# Tiny_UniProg_-_Arduino_Uno.net
KiCad netlist of a schematic drawn in EAGLE
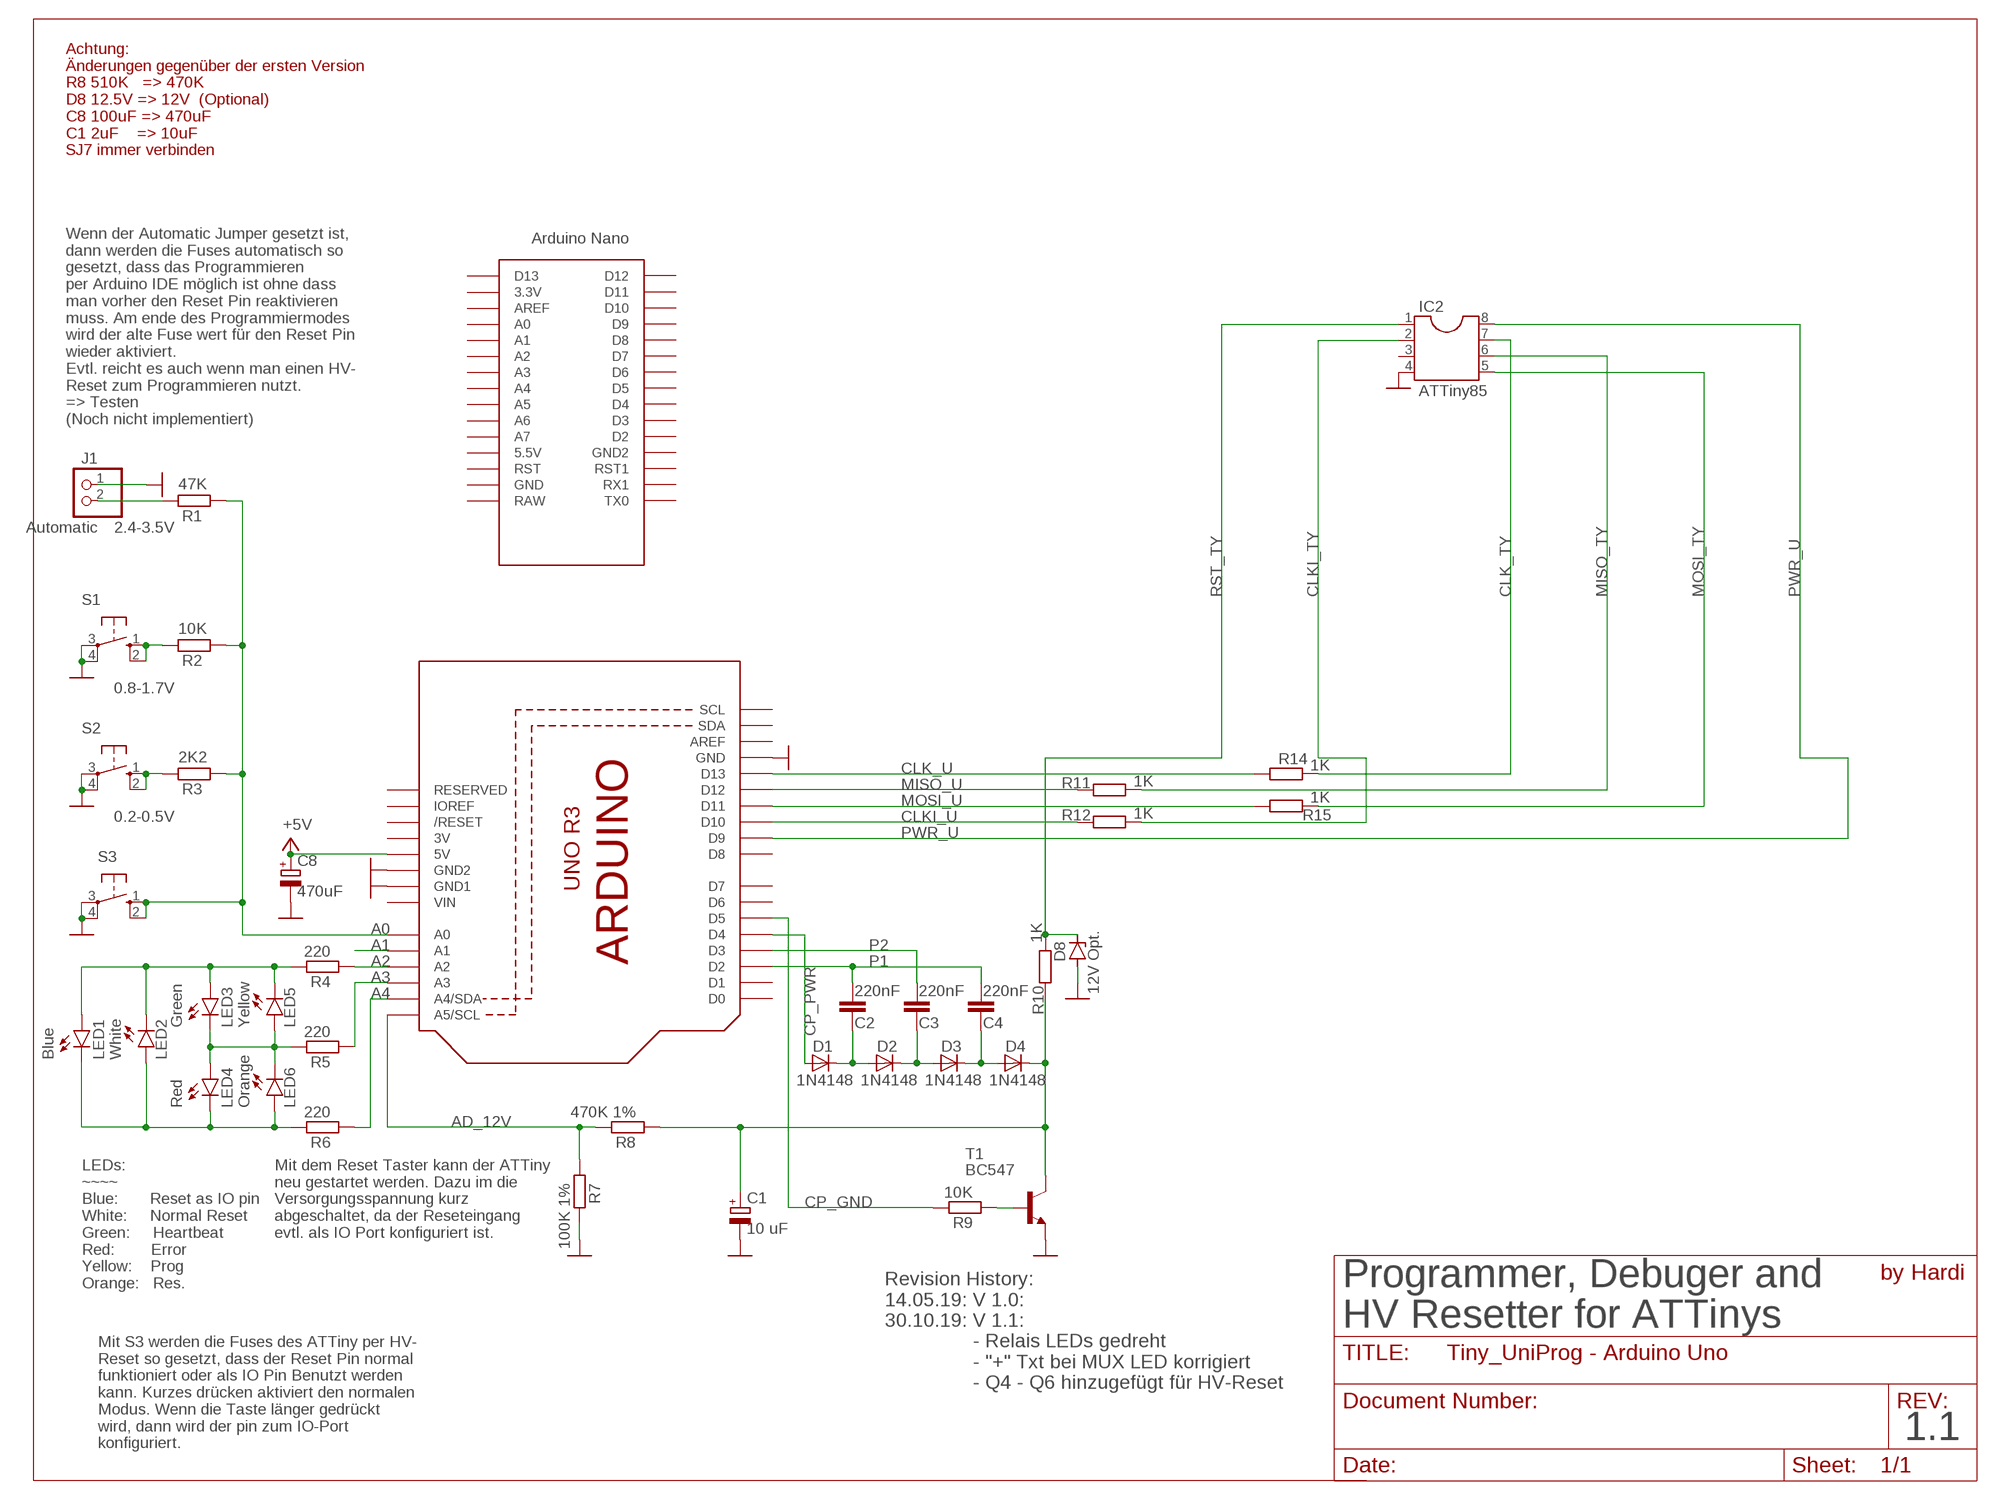
[diagram p0: schematic, sheet 1]

(export (version "E")
  (design (tool "Eeschema 10.0.6"))
  (components
    (comp (ref "C1")
      (value "10 uF")
      (footprint "eagle-import:E5-5")
      (libsource (lib "eagle-import") (part "CPOL-EUE5-5"))
    )
    (comp (ref "C2")
      (value "220nF")
      (footprint "eagle-import:C050-024X044")
      (libsource (lib "eagle-import") (part "C-EU050-024X044"))
    )
    (comp (ref "C3")
      (value "220nF")
      (footprint "eagle-import:C050-024X044")
      (libsource (lib "eagle-import") (part "C-EU050-024X044"))
    )
    (comp (ref "C4")
      (value "220nF")
      (footprint "eagle-import:C050-024X044")
      (libsource (lib "eagle-import") (part "C-EU050-024X044"))
    )
    (comp (ref "C8")
      (value "470uF")
      (footprint "eagle-import:E5-10,5")
      (libsource (lib "eagle-import") (part "CPOL-EUE5-10.5"))
    )
    (comp (ref "D1")
      (value "1N4148")
      (footprint "eagle-import:DO35-2")
      (libsource (lib "eagle-import") (part "1N4148DO35-2"))
    )
    (comp (ref "D2")
      (value "1N4148")
      (footprint "eagle-import:DO35-2")
      (libsource (lib "eagle-import") (part "1N4148DO35-2"))
    )
    (comp (ref "D3")
      (value "1N4148")
      (footprint "eagle-import:DO35-2")
      (libsource (lib "eagle-import") (part "1N4148DO35-2"))
    )
    (comp (ref "D4")
      (value "1N4148")
      (footprint "eagle-import:DO35-2")
      (libsource (lib "eagle-import") (part "1N4148DO35-2"))
    )
    (comp (ref "D8")
      (value "12V Opt.")
      (footprint "eagle-import:ZDIO-2.5")
      (libsource (lib "eagle-import") (part "ZENER-DIODEZD-2.5"))
    )
    (comp (ref "IC2")
      (value "ATTiny85")
      (footprint "eagle-import:DIL08")
      (libsource (lib "eagle-import") (part "DIL8"))
    )
    (comp (ref "J1")
      (value "Automatic")
      (footprint "eagle-import:1X02")
      (libsource (lib "eagle-import") (part "PINHD-1X2"))
    )
    (comp (ref "LED1")
      (value "Blue")
      (footprint "eagle-import:LED3MM")
      (libsource (lib "eagle-import") (part "LED3MM"))
    )
    (comp (ref "LED2")
      (value "White")
      (footprint "eagle-import:LED3MM")
      (libsource (lib "eagle-import") (part "LED3MM"))
    )
    (comp (ref "LED3")
      (value "Green")
      (footprint "eagle-import:LED3MM")
      (libsource (lib "eagle-import") (part "LED3MM"))
    )
    (comp (ref "LED4")
      (value "Red")
      (footprint "eagle-import:LED3MM")
      (libsource (lib "eagle-import") (part "LED3MM"))
    )
    (comp (ref "LED5")
      (value "Yellow")
      (footprint "eagle-import:LED3MM")
      (libsource (lib "eagle-import") (part "LED3MM"))
    )
    (comp (ref "LED6")
      (value "Orange")
      (footprint "eagle-import:LED3MM")
      (libsource (lib "eagle-import") (part "LED3MM"))
    )
    (comp (ref "R1")
      (value "47K")
      (footprint "eagle-import:0204_5")
      (libsource (lib "eagle-import") (part "R-EU_0204/5"))
    )
    (comp (ref "R2")
      (value "10K")
      (footprint "eagle-import:0204V")
      (libsource (lib "eagle-import") (part "R-EU_0204/2V"))
    )
    (comp (ref "R3")
      (value "2K2")
      (footprint "eagle-import:0204V")
      (libsource (lib "eagle-import") (part "R-EU_0204/2V"))
    )
    (comp (ref "R4")
      (value "220")
      (footprint "eagle-import:0204_5")
      (libsource (lib "eagle-import") (part "R-EU_0204/5"))
    )
    (comp (ref "R5")
      (value "220")
      (footprint "eagle-import:0204V")
      (libsource (lib "eagle-import") (part "R-EU_0204/2V"))
    )
    (comp (ref "R6")
      (value "220")
      (footprint "eagle-import:0204_5")
      (libsource (lib "eagle-import") (part "R-EU_0204/5"))
    )
    (comp (ref "R7")
      (value "100K 1%")
      (footprint "eagle-import:0204_7")
      (libsource (lib "eagle-import") (part "R-EU_0204/7"))
    )
    (comp (ref "R8")
      (value "470K 1%")
      (footprint "eagle-import:0204V")
      (libsource (lib "eagle-import") (part "R-EU_0204/2V"))
    )
    (comp (ref "R9")
      (value "10K")
      (footprint "eagle-import:0204_7")
      (libsource (lib "eagle-import") (part "R-EU_0204/7"))
    )
    (comp (ref "R10")
      (value "1K")
      (footprint "eagle-import:0207_15")
      (libsource (lib "eagle-import") (part "R-EU_0207/15"))
    )
    (comp (ref "R11")
      (value "1K")
      (footprint "eagle-import:0204V")
      (libsource (lib "eagle-import") (part "R-EU_0204/2V"))
    )
    (comp (ref "R12")
      (value "1K")
      (footprint "eagle-import:0207_7")
      (libsource (lib "eagle-import") (part "R-EU_0207/7"))
    )
    (comp (ref "R14")
      (value "1K")
      (footprint "eagle-import:0204V")
      (libsource (lib "eagle-import") (part "R-EU_0204/2V"))
    )
    (comp (ref "R15")
      (value "1K")
      (footprint "eagle-import:0204V")
      (libsource (lib "eagle-import") (part "R-EU_0204/2V"))
    )
    (comp (ref "S1")
      (value "10-XX")
      (footprint "eagle-import:B3F-10XX")
      (fields (field (name "MPN") "B3F-1000"))
      (libsource (lib "eagle-import") (part "10-XX"))
    )
    (comp (ref "S2")
      (value "10-XX")
      (footprint "eagle-import:B3F-10XX")
      (fields (field (name "MPN") "B3F-1000"))
      (libsource (lib "eagle-import") (part "10-XX"))
    )
    (comp (ref "S3")
      (value "10-XX")
      (footprint "eagle-import:B3F-10XX")
      (fields (field (name "MPN") "B3F-1000"))
      (libsource (lib "eagle-import") (part "10-XX"))
    )
    (comp (ref "T1")
      (value "BC547")
      (footprint "eagle-import:TO92")
      (libsource (lib "eagle-import") (part "BC547"))
    )
    (comp (ref "U$1")
      (value "NANO")
      (footprint "eagle-import:NANO")
      (libsource (lib "eagle-import") (part "NANO"))
    )
    (comp (ref "U1")
      (value "ARDUINOR3-DIMENSION")
      (footprint "eagle-import:ARDUINOR3")
      (libsource (lib "eagle-import") (part "ARDUINOR3-DIMENSION"))
    )
  )
  (nets
    (net (code "1") (name "+5V") (class "Default")
      (node (ref "C8") (pin "+") (pinfunction "+_+") (pintype "passive"))
      (node (ref "U1") (pin "5V") (pinfunction "5V_5V") (pintype "power_in"))
    )
    (net (code "2") (name "/3V") (class "Default")
      (node (ref "U1") (pin "3V") (pinfunction "3V_3V") (pintype "power_in"))
    )
    (net (code "3") (name "/A0") (class "Default")
      (node (ref "R1") (pin "1") (pinfunction "1_1") (pintype "passive"))
      (node (ref "R2") (pin "1") (pinfunction "1_1") (pintype "passive"))
      (node (ref "R3") (pin "1") (pinfunction "1_1") (pintype "passive"))
      (node (ref "S3") (pin "1") (pinfunction "S_1") (pintype "passive"))
      (node (ref "S3") (pin "2") (pinfunction "S1_2") (pintype "passive"))
      (node (ref "U1") (pin "A0") (pinfunction "A0_A0") (pintype "bidirectional"))
    )
    (net (code "4") (name "/A1") (class "Default")
      (node (ref "U1") (pin "A1") (pinfunction "A1_A1") (pintype "bidirectional"))
    )
    (net (code "5") (name "/A2") (class "Default")
      (node (ref "R4") (pin "1") (pinfunction "1_1") (pintype "passive"))
      (node (ref "U1") (pin "A2") (pinfunction "A2_A2") (pintype "bidirectional"))
    )
    (net (code "6") (name "/A3") (class "Default")
      (node (ref "R5") (pin "1") (pinfunction "1_1") (pintype "passive"))
      (node (ref "U1") (pin "A3") (pinfunction "A3_A3") (pintype "bidirectional"))
    )
    (net (code "7") (name "/A4") (class "Default")
      (node (ref "R6") (pin "1") (pinfunction "1_1") (pintype "passive"))
      (node (ref "U1") (pin "A4") (pinfunction "A4/SDA_A4") (pintype "bidirectional"))
    )
    (net (code "8") (name "/AD_12V") (class "Default")
      (node (ref "R7") (pin "1") (pinfunction "1_1") (pintype "passive"))
      (node (ref "R8") (pin "2") (pinfunction "2_2") (pintype "passive"))
      (node (ref "U1") (pin "A5") (pinfunction "A5/SCL_A5") (pintype "bidirectional"))
    )
    (net (code "9") (name "/CLKI_TY") (class "Default")
      (node (ref "IC2") (pin "2") (pinfunction "2_2") (pintype "passive"))
      (node (ref "R12") (pin "2") (pinfunction "2_2") (pintype "passive"))
    )
    (net (code "10") (name "/CLKI_U") (class "Default")
      (node (ref "R12") (pin "1") (pinfunction "1_1") (pintype "passive"))
      (node (ref "U1") (pin "D10") (pinfunction "D10_D10") (pintype "bidirectional"))
    )
    (net (code "11") (name "/CLK_TY") (class "Default")
      (node (ref "IC2") (pin "7") (pinfunction "7_7") (pintype "passive"))
      (node (ref "R14") (pin "2") (pinfunction "2_2") (pintype "passive"))
    )
    (net (code "12") (name "/CLK_U") (class "Default")
      (node (ref "R14") (pin "1") (pinfunction "1_1") (pintype "passive"))
      (node (ref "U1") (pin "D13") (pinfunction "D13_D13") (pintype "bidirectional"))
    )
    (net (code "13") (name "/CP_GND") (class "Default")
      (node (ref "R9") (pin "2") (pinfunction "2_2") (pintype "passive"))
      (node (ref "U1") (pin "D5") (pinfunction "D5_D5") (pintype "bidirectional"))
    )
    (net (code "14") (name "/CP_PWR") (class "Default")
      (node (ref "D1") (pin "A") (pinfunction "A_A") (pintype "passive"))
      (node (ref "U1") (pin "D4") (pinfunction "D4_D4") (pintype "bidirectional"))
    )
    (net (code "15") (name "/MISO_TY") (class "Default")
      (node (ref "IC2") (pin "6") (pinfunction "6_6") (pintype "passive"))
      (node (ref "R11") (pin "2") (pinfunction "2_2") (pintype "passive"))
    )
    (net (code "16") (name "/MISO_U") (class "Default")
      (node (ref "R11") (pin "1") (pinfunction "1_1") (pintype "passive"))
      (node (ref "U1") (pin "D12") (pinfunction "D12_D12") (pintype "bidirectional"))
    )
    (net (code "17") (name "/MOSI_TY") (class "Default")
      (node (ref "IC2") (pin "5") (pinfunction "5_5") (pintype "passive"))
      (node (ref "R15") (pin "2") (pinfunction "2_2") (pintype "passive"))
    )
    (net (code "18") (name "/MOSI_U") (class "Default")
      (node (ref "R15") (pin "1") (pinfunction "1_1") (pintype "passive"))
      (node (ref "U1") (pin "D11") (pinfunction "D11_D11") (pintype "bidirectional"))
    )
    (net (code "19") (name "/P1") (class "Default")
      (node (ref "C2") (pin "1") (pinfunction "1_1") (pintype "passive"))
      (node (ref "C4") (pin "1") (pinfunction "1_1") (pintype "passive"))
      (node (ref "U1") (pin "D2") (pinfunction "D2_D2") (pintype "bidirectional"))
    )
    (net (code "20") (name "/P2") (class "Default")
      (node (ref "C3") (pin "1") (pinfunction "1_1") (pintype "passive"))
      (node (ref "U1") (pin "D3") (pinfunction "D3_D3") (pintype "bidirectional"))
    )
    (net (code "21") (name "/PWR_U") (class "Default")
      (node (ref "IC2") (pin "8") (pinfunction "8_8") (pintype "passive"))
      (node (ref "U1") (pin "D9") (pinfunction "D9_D9") (pintype "bidirectional"))
    )
    (net (code "22") (name "/RST_TY") (class "Default")
      (node (ref "D8") (pin "C") (pinfunction "C_C") (pintype "passive"))
      (node (ref "IC2") (pin "1") (pinfunction "1_1") (pintype "passive"))
      (node (ref "R10") (pin "1") (pinfunction "1_1") (pintype "passive"))
    )
    (net (code "23") (name "/VIN") (class "Default")
      (node (ref "U1") (pin "VIN") (pinfunction "VIN_VIN") (pintype "power_in"))
    )
    (net (code "24") (name "GND") (class "Default")
      (node (ref "C1") (pin "-") (pinfunction "-_-") (pintype "passive"))
      (node (ref "C8") (pin "-") (pinfunction "-_-") (pintype "passive"))
      (node (ref "D8") (pin "A") (pinfunction "A_A") (pintype "passive"))
      (node (ref "IC2") (pin "4") (pinfunction "4_4") (pintype "passive"))
      (node (ref "J1") (pin "1") (pinfunction "1_1") (pintype "passive"))
      (node (ref "R7") (pin "2") (pinfunction "2_2") (pintype "passive"))
      (node (ref "S1") (pin "3") (pinfunction "P_3") (pintype "passive"))
      (node (ref "S1") (pin "4") (pinfunction "P1_4") (pintype "passive"))
      (node (ref "S2") (pin "3") (pinfunction "P_3") (pintype "passive"))
      (node (ref "S2") (pin "4") (pinfunction "P1_4") (pintype "passive"))
      (node (ref "S3") (pin "3") (pinfunction "P_3") (pintype "passive"))
      (node (ref "S3") (pin "4") (pinfunction "P1_4") (pintype "passive"))
      (node (ref "T1") (pin "1") (pinfunction "E_1") (pintype "passive"))
      (node (ref "U1") (pin "GND") (pinfunction "GND_GND") (pintype "power_in"))
      (node (ref "U1") (pin "GND1") (pinfunction "GND1_GND1") (pintype "power_in"))
      (node (ref "U1") (pin "GND2") (pinfunction "GND2_GND2") (pintype "power_in"))
    )
    (net (code "25") (name "Net-(C2-Pad2)") (class "Default")
      (node (ref "C2") (pin "2") (pinfunction "2_2") (pintype "passive"))
      (node (ref "D1") (pin "C") (pinfunction "C_C") (pintype "passive"))
      (node (ref "D2") (pin "A") (pinfunction "A_A") (pintype "passive"))
    )
    (net (code "26") (name "Net-(C3-Pad2)") (class "Default")
      (node (ref "C3") (pin "2") (pinfunction "2_2") (pintype "passive"))
      (node (ref "D2") (pin "C") (pinfunction "C_C") (pintype "passive"))
      (node (ref "D3") (pin "A") (pinfunction "A_A") (pintype "passive"))
    )
    (net (code "27") (name "Net-(C4-Pad2)") (class "Default")
      (node (ref "C4") (pin "2") (pinfunction "2_2") (pintype "passive"))
      (node (ref "D3") (pin "C") (pinfunction "C_C") (pintype "passive"))
      (node (ref "D4") (pin "A") (pinfunction "A_A") (pintype "passive"))
    )
    (net (code "28") (name "Net-(J1-Pad2)") (class "Default")
      (node (ref "J1") (pin "2") (pinfunction "2_2") (pintype "passive"))
      (node (ref "R1") (pin "2") (pinfunction "2_2") (pintype "passive"))
    )
    (net (code "29") (name "Net-(LED1-C)") (class "Default")
      (node (ref "LED1") (pin "K") (pinfunction "C_K") (pintype "passive"))
      (node (ref "LED2") (pin "A") (pinfunction "A_A") (pintype "passive"))
      (node (ref "LED4") (pin "K") (pinfunction "C_K") (pintype "passive"))
      (node (ref "LED6") (pin "A") (pinfunction "A_A") (pintype "passive"))
      (node (ref "R6") (pin "2") (pinfunction "2_2") (pintype "passive"))
    )
    (net (code "30") (name "Net-(LED2-C)") (class "Default")
      (node (ref "LED1") (pin "A") (pinfunction "A_A") (pintype "passive"))
      (node (ref "LED2") (pin "K") (pinfunction "C_K") (pintype "passive"))
      (node (ref "LED3") (pin "A") (pinfunction "A_A") (pintype "passive"))
      (node (ref "LED5") (pin "K") (pinfunction "C_K") (pintype "passive"))
      (node (ref "R4") (pin "2") (pinfunction "2_2") (pintype "passive"))
    )
    (net (code "31") (name "Net-(LED3-C)") (class "Default")
      (node (ref "LED3") (pin "K") (pinfunction "C_K") (pintype "passive"))
      (node (ref "LED4") (pin "A") (pinfunction "A_A") (pintype "passive"))
      (node (ref "LED5") (pin "A") (pinfunction "A_A") (pintype "passive"))
      (node (ref "LED6") (pin "K") (pinfunction "C_K") (pintype "passive"))
      (node (ref "R5") (pin "2") (pinfunction "2_2") (pintype "passive"))
    )
    (net (code "32") (name "Net-(S1-S)") (class "Default")
      (node (ref "R2") (pin "2") (pinfunction "2_2") (pintype "passive"))
      (node (ref "S1") (pin "1") (pinfunction "S_1") (pintype "passive"))
      (node (ref "S1") (pin "2") (pinfunction "S1_2") (pintype "passive"))
    )
    (net (code "33") (name "Net-(S2-S)") (class "Default")
      (node (ref "R3") (pin "2") (pinfunction "2_2") (pintype "passive"))
      (node (ref "S2") (pin "1") (pinfunction "S_1") (pintype "passive"))
      (node (ref "S2") (pin "2") (pinfunction "S1_2") (pintype "passive"))
    )
    (net (code "34") (name "Net-(T1-B)") (class "Default")
      (node (ref "R9") (pin "1") (pinfunction "1_1") (pintype "passive"))
      (node (ref "T1") (pin "2") (pinfunction "B_2") (pintype "passive"))
    )
    (net (code "35") (name "Net-(T1-C)") (class "Default")
      (node (ref "C1") (pin "+") (pinfunction "+_+") (pintype "passive"))
      (node (ref "D4") (pin "C") (pinfunction "C_C") (pintype "passive"))
      (node (ref "R10") (pin "2") (pinfunction "2_2") (pintype "passive"))
      (node (ref "R8") (pin "1") (pinfunction "1_1") (pintype "passive"))
      (node (ref "T1") (pin "3") (pinfunction "C_3") (pintype "passive"))
    )
    (net (code "36") (name "unconnected-(IC2-Pad3)") (class "Default")
      (node (ref "IC2") (pin "3") (pinfunction "3_3") (pintype "passive"))
    )
    (net (code "37") (name "unconnected-(U$1-5.5V-Pad5V)") (class "Default")
      (node (ref "U$1") (pin "5V") (pinfunction "5.5V_5V") (pintype "bidirectional"))
    )
    (net (code "38") (name "unconnected-(U$1-GND2-PadGND1)") (class "Default")
      (node (ref "U$1") (pin "GND1") (pinfunction "GND2_GND1") (pintype "bidirectional"))
    )
    (net (code "39") (name "unconnected-(U$1-Pad3.3V)") (class "Default")
      (node (ref "U$1") (pin "3.3V") (pinfunction "3.3V_3.3V") (pintype "bidirectional"))
    )
    (net (code "40") (name "unconnected-(U$1-PadA0)") (class "Default")
      (node (ref "U$1") (pin "A0") (pinfunction "A0_A0") (pintype "bidirectional"))
    )
    (net (code "41") (name "unconnected-(U$1-PadA1)") (class "Default")
      (node (ref "U$1") (pin "A1") (pinfunction "A1_A1") (pintype "bidirectional"))
    )
    (net (code "42") (name "unconnected-(U$1-PadA2)") (class "Default")
      (node (ref "U$1") (pin "A2") (pinfunction "A2_A2") (pintype "bidirectional"))
    )
    (net (code "43") (name "unconnected-(U$1-PadA3)") (class "Default")
      (node (ref "U$1") (pin "A3") (pinfunction "A3_A3") (pintype "bidirectional"))
    )
    (net (code "44") (name "unconnected-(U$1-PadA4)") (class "Default")
      (node (ref "U$1") (pin "A4") (pinfunction "A4_A4") (pintype "bidirectional"))
    )
    (net (code "45") (name "unconnected-(U$1-PadA5)") (class "Default")
      (node (ref "U$1") (pin "A5") (pinfunction "A5_A5") (pintype "bidirectional"))
    )
    (net (code "46") (name "unconnected-(U$1-PadA6)") (class "Default")
      (node (ref "U$1") (pin "A6") (pinfunction "A6_A6") (pintype "bidirectional"))
    )
    (net (code "47") (name "unconnected-(U$1-PadA7)") (class "Default")
      (node (ref "U$1") (pin "A7") (pinfunction "A7_A7") (pintype "bidirectional"))
    )
    (net (code "48") (name "unconnected-(U$1-PadAREF)") (class "Default")
      (node (ref "U$1") (pin "AREF") (pinfunction "AREF_AREF") (pintype "bidirectional"))
    )
    (net (code "49") (name "unconnected-(U$1-PadD2)") (class "Default")
      (node (ref "U$1") (pin "D2") (pinfunction "D2_D2") (pintype "bidirectional"))
    )
    (net (code "50") (name "unconnected-(U$1-PadD3)") (class "Default")
      (node (ref "U$1") (pin "D3") (pinfunction "D3_D3") (pintype "bidirectional"))
    )
    (net (code "51") (name "unconnected-(U$1-PadD4)") (class "Default")
      (node (ref "U$1") (pin "D4") (pinfunction "D4_D4") (pintype "bidirectional"))
    )
    (net (code "52") (name "unconnected-(U$1-PadD5)") (class "Default")
      (node (ref "U$1") (pin "D5") (pinfunction "D5_D5") (pintype "bidirectional"))
    )
    (net (code "53") (name "unconnected-(U$1-PadD6)") (class "Default")
      (node (ref "U$1") (pin "D6") (pinfunction "D6_D6") (pintype "bidirectional"))
    )
    (net (code "54") (name "unconnected-(U$1-PadD7)") (class "Default")
      (node (ref "U$1") (pin "D7") (pinfunction "D7_D7") (pintype "bidirectional"))
    )
    (net (code "55") (name "unconnected-(U$1-PadD8)") (class "Default")
      (node (ref "U$1") (pin "D8") (pinfunction "D8_D8") (pintype "bidirectional"))
    )
    (net (code "56") (name "unconnected-(U$1-PadD9)") (class "Default")
      (node (ref "U$1") (pin "D9") (pinfunction "D9_D9") (pintype "bidirectional"))
    )
    (net (code "57") (name "unconnected-(U$1-PadD10)") (class "Default")
      (node (ref "U$1") (pin "D10") (pinfunction "D10_D10") (pintype "bidirectional"))
    )
    (net (code "58") (name "unconnected-(U$1-PadD11)") (class "Default")
      (node (ref "U$1") (pin "D11") (pinfunction "D11_D11") (pintype "bidirectional"))
    )
    (net (code "59") (name "unconnected-(U$1-PadD12)") (class "Default")
      (node (ref "U$1") (pin "D12") (pinfunction "D12_D12") (pintype "bidirectional"))
    )
    (net (code "60") (name "unconnected-(U$1-PadD13)") (class "Default")
      (node (ref "U$1") (pin "D13") (pinfunction "D13_D13") (pintype "bidirectional"))
    )
    (net (code "61") (name "unconnected-(U$1-PadGND)") (class "Default")
      (node (ref "U$1") (pin "GND") (pinfunction "GND_GND") (pintype "bidirectional"))
    )
    (net (code "62") (name "unconnected-(U$1-PadICSP1)") (class "Default")
      (node (ref "U$1") (pin "ICSP1") (pinfunction "ICSP1_ICSP1") (pintype "bidirectional"))
    )
    (net (code "63") (name "unconnected-(U$1-PadICSP2)") (class "Default")
      (node (ref "U$1") (pin "ICSP2") (pinfunction "ICSP2_ICSP2") (pintype "bidirectional"))
    )
    (net (code "64") (name "unconnected-(U$1-PadICSP3)") (class "Default")
      (node (ref "U$1") (pin "ICSP3") (pinfunction "ICSP3_ICSP3") (pintype "bidirectional"))
    )
    (net (code "65") (name "unconnected-(U$1-PadICSP4)") (class "Default")
      (node (ref "U$1") (pin "ICSP4") (pinfunction "ICSP4_ICSP4") (pintype "bidirectional"))
    )
    (net (code "66") (name "unconnected-(U$1-PadICSP5)") (class "Default")
      (node (ref "U$1") (pin "ICSP5") (pinfunction "ICSP5_ICSP5") (pintype "bidirectional"))
    )
    (net (code "67") (name "unconnected-(U$1-PadICSP6)") (class "Default")
      (node (ref "U$1") (pin "ICSP6") (pinfunction "ICSP6_ICSP6") (pintype "bidirectional"))
    )
    (net (code "68") (name "unconnected-(U$1-PadRAW)") (class "Default")
      (node (ref "U$1") (pin "RAW") (pinfunction "RAW_RAW") (pintype "bidirectional"))
    )
    (net (code "69") (name "unconnected-(U$1-PadRST)") (class "Default")
      (node (ref "U$1") (pin "RST") (pinfunction "RST_RST") (pintype "bidirectional"))
    )
    (net (code "70") (name "unconnected-(U$1-PadRST1)") (class "Default")
      (node (ref "U$1") (pin "RST1") (pinfunction "RST1_RST1") (pintype "bidirectional"))
    )
    (net (code "71") (name "unconnected-(U$1-PadRX1)") (class "Default")
      (node (ref "U$1") (pin "RX1") (pinfunction "RX1_RX1") (pintype "bidirectional"))
    )
    (net (code "72") (name "unconnected-(U$1-PadTX0)") (class "Default")
      (node (ref "U$1") (pin "TX0") (pinfunction "TX0_TX0") (pintype "bidirectional"))
    )
    (net (code "73") (name "unconnected-(U1-PadAREF)") (class "Default")
      (node (ref "U1") (pin "AREF") (pinfunction "AREF_AREF") (pintype "bidirectional"))
    )
    (net (code "74") (name "unconnected-(U1-PadD0)") (class "Default")
      (node (ref "U1") (pin "D0") (pinfunction "D0_D0") (pintype "bidirectional"))
    )
    (net (code "75") (name "unconnected-(U1-PadD1)") (class "Default")
      (node (ref "U1") (pin "D1") (pinfunction "D1_D1") (pintype "bidirectional"))
    )
    (net (code "76") (name "unconnected-(U1-PadD6)") (class "Default")
      (node (ref "U1") (pin "D6") (pinfunction "D6_D6") (pintype "bidirectional"))
    )
    (net (code "77") (name "unconnected-(U1-PadD7)") (class "Default")
      (node (ref "U1") (pin "D7") (pinfunction "D7_D7") (pintype "bidirectional"))
    )
    (net (code "78") (name "unconnected-(U1-PadD8)") (class "Default")
      (node (ref "U1") (pin "D8") (pinfunction "D8_D8") (pintype "bidirectional"))
    )
    (net (code "79") (name "unconnected-(U1-PadIOREF)") (class "Default")
      (node (ref "U1") (pin "IOREF") (pinfunction "IOREF_IOREF") (pintype "output"))
    )
    (net (code "80") (name "unconnected-(U1-PadRESERVED)") (class "Default")
      (node (ref "U1") (pin "RESERVED") (pinfunction "RESERVED_RESERVED") (pintype "no_connect"))
    )
    (net (code "81") (name "unconnected-(U1-PadSCL)") (class "Default")
      (node (ref "U1") (pin "SCL") (pinfunction "SCL_SCL") (pintype "bidirectional"))
    )
    (net (code "82") (name "unconnected-(U1-PadSDA)") (class "Default")
      (node (ref "U1") (pin "SDA") (pinfunction "SDA_SDA") (pintype "bidirectional"))
    )
    (net (code "83") (name "unconnected-(U1-{slash}RESET-PadRESET)") (class "Default")
      (node (ref "U1") (pin "RESET") (pinfunction "/RESET_RESET") (pintype "bidirectional"))
    )
  )
)
